# MCU_external_components.net
KiCad netlist of a schematic drawn in Altium Designer
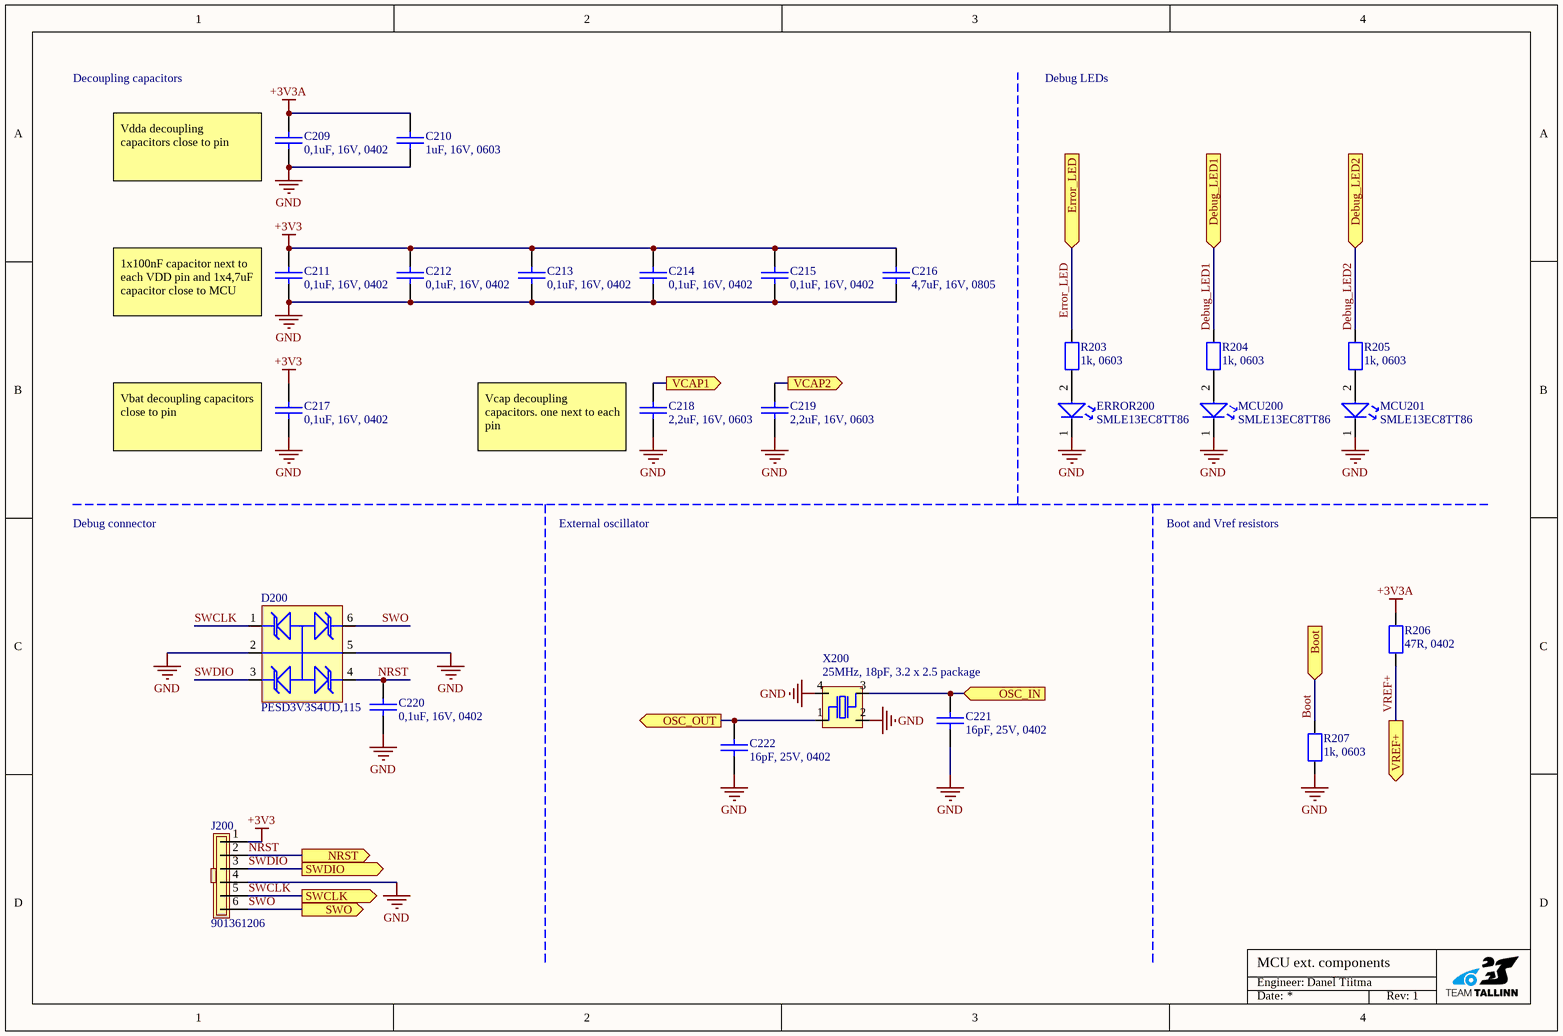
[diagram p0: MCU_external_components.SchDoc]

(export (version "E")
  (design (tool "Eeschema 10.0.6"))
  (components
    (comp (ref "C209")
      (value "0,1uF, 16V, 0402")
      (footprint "CAP [0402] 1005")
      (description "Default capacitor part")
      (libsource (lib "Formula Student Team Tallinn (Estonia)") (part "Capacitor"))
    )
    (comp (ref "C210")
      (value "1uF, 16V, 0603")
      (footprint "CAP [0603] 1608")
      (description "Default capacitor part")
      (libsource (lib "Formula Student Team Tallinn (Estonia)") (part "Capacitor"))
    )
    (comp (ref "C211")
      (value "0,1uF, 16V, 0402")
      (footprint "CAP [0402] 1005")
      (description "Default capacitor part")
      (libsource (lib "Formula Student Team Tallinn (Estonia)") (part "Capacitor"))
    )
    (comp (ref "C212")
      (value "0,1uF, 16V, 0402")
      (footprint "CAP [0402] 1005")
      (description "Default capacitor part")
      (libsource (lib "Formula Student Team Tallinn (Estonia)") (part "Capacitor"))
    )
    (comp (ref "C213")
      (value "0,1uF, 16V, 0402")
      (footprint "CAP [0402] 1005")
      (description "Default capacitor part")
      (libsource (lib "Formula Student Team Tallinn (Estonia)") (part "Capacitor"))
    )
    (comp (ref "C214")
      (value "0,1uF, 16V, 0402")
      (footprint "CAP [0402] 1005")
      (description "Default capacitor part")
      (libsource (lib "Formula Student Team Tallinn (Estonia)") (part "Capacitor"))
    )
    (comp (ref "C215")
      (value "0,1uF, 16V, 0402")
      (footprint "CAP [0402] 1005")
      (description "Default capacitor part")
      (libsource (lib "Formula Student Team Tallinn (Estonia)") (part "Capacitor"))
    )
    (comp (ref "C216")
      (value "4,7uF, 16V, 0805")
      (footprint "CAP [0805] 2012")
      (description "Default capacitor part")
      (libsource (lib "Formula Student Team Tallinn (Estonia)") (part "Capacitor"))
    )
    (comp (ref "C217")
      (value "0,1uF, 16V, 0402")
      (footprint "CAP [0402] 1005")
      (description "Default capacitor part")
      (libsource (lib "Formula Student Team Tallinn (Estonia)") (part "Capacitor"))
    )
    (comp (ref "C218")
      (value "2,2uF, 16V, 0603")
      (footprint "CAP [0603] 1608")
      (fields
        (field (name "MANUFACTURER") "TDK")
        (field (name "MANUFACTURER PART NUMBER") "CGA3E1X5R1C225M080AC")
      )
      (libsource (lib "Formula Student Team Tallinn (Estonia)") (part "Capacitor"))
    )
    (comp (ref "C219")
      (value "2,2uF, 16V, 0603")
      (footprint "CAP [0603] 1608")
      (fields
        (field (name "MANUFACTURER") "TDK")
        (field (name "MANUFACTURER PART NUMBER") "CGA3E1X5R1C225M080AC")
      )
      (libsource (lib "Formula Student Team Tallinn (Estonia)") (part "Capacitor"))
    )
    (comp (ref "C220")
      (value "0,1uF, 16V, 0402")
      (footprint "CAP [0402] 1005")
      (description "Default capacitor part")
      (libsource (lib "Formula Student Team Tallinn (Estonia)") (part "Capacitor"))
    )
    (comp (ref "C221")
      (value "16pF, 25V, 0402")
      (footprint "CAP [0402] 1005")
      (fields
        (field (name "MANUFACTURER PART NUMBER") "C0402C160K3HACAUTO")
        (field (name "MANUFACTURER") "KEMET")
      )
      (libsource (lib "Formula Student Team Tallinn (Estonia)") (part "Capacitor"))
    )
    (comp (ref "C222")
      (value "16pF, 25V, 0402")
      (footprint "CAP [0402] 1005")
      (fields
        (field (name "MANUFACTURER PART NUMBER") "C0402C160K3HACAUTO")
        (field (name "MANUFACTURER") "KEMET")
      )
      (libsource (lib "Formula Student Team Tallinn (Estonia)") (part "Capacitor"))
    )
    (comp (ref "D200")
      (value "PESD3V3S4UD,115")
      (footprint "SOT23-6")
      (description "Trans Voltage Suppressor Diode, 200W, 3.3V V(RWM), Unidirectional, 4 Element, Silicon")
      (fields (field (name "MANUFACTURER") "Nexperia"))
      (libsource (lib "Formula Student Team Tallinn (Estonia)") (part "TVS diode array"))
    )
    (comp (ref "ERROR200")
      (value "SMLE13EC8TT86")
      (footprint "LED [0603] 1608")
      (description "Single Color LED, Green, Colorless Transparent, 1.2mm")
      (libsource (lib "Formula Student Team Tallinn (Estonia)") (part "Diode LED"))
    )
    (comp (ref "J200")
      (value "901361206")
      (footprint "901361206")
      (fields (field (name "MANUFACTURER PART NUMBER") "90136-1206") (field (name "MANUFACTURER") "Molex"))
      (libsource (lib "Formula Student Team Tallinn (Estonia)") (part "Connector C-Grid III 1x6"))
    )
    (comp (ref "MCU200")
      (value "SMLE13EC8TT86")
      (footprint "LED [0603] 1608")
      (description "Single Color LED, Green, Colorless Transparent, 1.2mm")
      (libsource (lib "Formula Student Team Tallinn (Estonia)") (part "Diode LED"))
    )
    (comp (ref "MCU201")
      (value "SMLE13EC8TT86")
      (footprint "LED [0603] 1608")
      (description "Single Color LED, Green, Colorless Transparent, 1.2mm")
      (libsource (lib "Formula Student Team Tallinn (Estonia)") (part "Diode LED"))
    )
    (comp (ref "R203")
      (value "1k, 0603")
      (footprint "RES [0603] 1608")
      (description "Standard resistor part")
      (libsource (lib "Formula Student Team Tallinn (Estonia)") (part "Resistor"))
    )
    (comp (ref "R204")
      (value "1k, 0603")
      (footprint "RES [0603] 1608")
      (description "Standard resistor part")
      (libsource (lib "Formula Student Team Tallinn (Estonia)") (part "Resistor"))
    )
    (comp (ref "R205")
      (value "1k, 0603")
      (footprint "RES [0603] 1608")
      (description "Standard resistor part")
      (libsource (lib "Formula Student Team Tallinn (Estonia)") (part "Resistor"))
    )
    (comp (ref "R206")
      (value "47R, 0402")
      (footprint "RES [0402] 1005")
      (description "Standard resistor part")
      (libsource (lib "Formula Student Team Tallinn (Estonia)") (part "Resistor"))
    )
    (comp (ref "R207")
      (value "1k, 0603")
      (footprint "RES [0603] 1608")
      (description "Standard resistor part")
      (libsource (lib "Formula Student Team Tallinn (Estonia)") (part "Resistor"))
    )
    (comp (ref "X200")
      (value "25MHz, 18pF, 3.2 x 2.5 package")
      (footprint "Crystal 3.2x2.5mm")
      (description "Crystal 25MHz ±20ppm (Tol) ±30ppm (Stability) 18pF FUND 60Ohm 4-Pin Ultra Mini-CSMD T/R")
      (fields
        (field (name "MANUFACTURER PART NUMBER") "ABM8G-25.000MHZ-18-D2Y-T")
        (field (name "MANUFACTURER") "ABRACON")
      )
      (libsource (lib "Formula Student Team Tallinn (Estonia)") (part "Crystal 4-pin"))
    )
  )
  (nets
    (net (code "1") (name "+3V3") (class "Default")
      (node (ref "C211") (pin "2") (pinfunction "2_2") (pintype "passive"))
      (node (ref "C212") (pin "2") (pinfunction "2_2") (pintype "passive"))
      (node (ref "C213") (pin "2") (pinfunction "2_2") (pintype "passive"))
      (node (ref "C214") (pin "2") (pinfunction "2_2") (pintype "passive"))
      (node (ref "C215") (pin "2") (pinfunction "2_2") (pintype "passive"))
      (node (ref "C216") (pin "2") (pinfunction "2_2") (pintype "passive"))
      (node (ref "C217") (pin "2") (pinfunction "2_2") (pintype "passive"))
      (node (ref "J200") (pin "1") (pinfunction "1_1") (pintype "passive"))
    )
    (net (code "2") (name "+3V3A") (class "Default")
      (node (ref "C209") (pin "2") (pinfunction "2_2") (pintype "passive"))
      (node (ref "C210") (pin "2") (pinfunction "2_2") (pintype "passive"))
      (node (ref "R206") (pin "2") (pinfunction "2_2") (pintype "passive"))
    )
    (net (code "3") (name "/Boot") (class "Default")
      (node (ref "R207") (pin "2") (pinfunction "2_2") (pintype "passive"))
    )
    (net (code "4") (name "/Debug_LED1") (class "Default")
      (node (ref "R204") (pin "2") (pinfunction "2_2") (pintype "passive"))
    )
    (net (code "5") (name "/Debug_LED2") (class "Default")
      (node (ref "R205") (pin "2") (pinfunction "2_2") (pintype "passive"))
    )
    (net (code "6") (name "/Error_LED") (class "Default")
      (node (ref "R203") (pin "2") (pinfunction "2_2") (pintype "passive"))
    )
    (net (code "7") (name "/NRST") (class "Default")
      (node (ref "C220") (pin "1") (pinfunction "1_1") (pintype "passive"))
      (node (ref "D200") (pin "4") (pinfunction "K3_4") (pintype "passive"))
      (node (ref "J200") (pin "2") (pinfunction "2_2") (pintype "passive"))
    )
    (net (code "8") (name "/OSC_IN") (class "Default")
      (node (ref "C221") (pin "1") (pinfunction "1_1") (pintype "passive"))
      (node (ref "X200") (pin "3") (pinfunction "3_3") (pintype "passive"))
    )
    (net (code "9") (name "/OSC_OUT") (class "Default")
      (node (ref "C222") (pin "1") (pinfunction "1_1") (pintype "passive"))
      (node (ref "X200") (pin "1") (pinfunction "1_1") (pintype "passive"))
    )
    (net (code "10") (name "/SWCLK") (class "Default")
      (node (ref "D200") (pin "1") (pinfunction "K1_1") (pintype "passive"))
      (node (ref "J200") (pin "5") (pinfunction "5_5") (pintype "passive"))
    )
    (net (code "11") (name "/SWDIO") (class "Default")
      (node (ref "D200") (pin "3") (pinfunction "K2_3") (pintype "passive"))
      (node (ref "J200") (pin "3") (pinfunction "3_3") (pintype "passive"))
    )
    (net (code "12") (name "/SWO") (class "Default")
      (node (ref "D200") (pin "6") (pinfunction "K4_6") (pintype "passive"))
      (node (ref "J200") (pin "6") (pinfunction "6_6") (pintype "passive"))
    )
    (net (code "13") (name "/VCAP1") (class "Default")
      (node (ref "C218") (pin "1") (pinfunction "1_1") (pintype "passive"))
    )
    (net (code "14") (name "/VCAP2") (class "Default")
      (node (ref "C219") (pin "1") (pinfunction "1_1") (pintype "passive"))
    )
    (net (code "15") (name "/VREF+") (class "Default")
      (node (ref "R206") (pin "1") (pinfunction "1_1") (pintype "passive"))
    )
    (net (code "16") (name "GND") (class "Default")
      (node (ref "C209") (pin "1") (pinfunction "1_1") (pintype "passive"))
      (node (ref "C210") (pin "1") (pinfunction "1_1") (pintype "passive"))
      (node (ref "C211") (pin "1") (pinfunction "1_1") (pintype "passive"))
      (node (ref "C212") (pin "1") (pinfunction "1_1") (pintype "passive"))
      (node (ref "C213") (pin "1") (pinfunction "1_1") (pintype "passive"))
      (node (ref "C214") (pin "1") (pinfunction "1_1") (pintype "passive"))
      (node (ref "C215") (pin "1") (pinfunction "1_1") (pintype "passive"))
      (node (ref "C216") (pin "1") (pinfunction "1_1") (pintype "passive"))
      (node (ref "C217") (pin "1") (pinfunction "1_1") (pintype "passive"))
      (node (ref "C218") (pin "2") (pinfunction "2_2") (pintype "passive"))
      (node (ref "C219") (pin "2") (pinfunction "2_2") (pintype "passive"))
      (node (ref "C220") (pin "2") (pinfunction "2_2") (pintype "passive"))
      (node (ref "C221") (pin "2") (pinfunction "2_2") (pintype "passive"))
      (node (ref "C222") (pin "2") (pinfunction "2_2") (pintype "passive"))
      (node (ref "D200") (pin "2") (pinfunction "GND_2") (pintype "passive"))
      (node (ref "D200") (pin "5") (pinfunction "GND_5") (pintype "passive"))
      (node (ref "ERROR200") (pin "1") (pinfunction "1_1") (pintype "passive"))
      (node (ref "J200") (pin "4") (pinfunction "4_4") (pintype "passive"))
      (node (ref "MCU200") (pin "1") (pinfunction "1_1") (pintype "passive"))
      (node (ref "MCU201") (pin "1") (pinfunction "1_1") (pintype "passive"))
      (node (ref "R207") (pin "1") (pinfunction "1_1") (pintype "passive"))
      (node (ref "X200") (pin "2") (pinfunction "2_2") (pintype "passive"))
      (node (ref "X200") (pin "4") (pinfunction "4_4") (pintype "passive"))
    )
    (net (code "17") (name "Net-(ERROR200-Pad2)") (class "Default")
      (node (ref "ERROR200") (pin "2") (pinfunction "2_2") (pintype "passive"))
      (node (ref "R203") (pin "1") (pinfunction "1_1") (pintype "passive"))
    )
    (net (code "18") (name "Net-(MCU200-Pad2)") (class "Default")
      (node (ref "MCU200") (pin "2") (pinfunction "2_2") (pintype "passive"))
      (node (ref "R204") (pin "1") (pinfunction "1_1") (pintype "passive"))
    )
    (net (code "19") (name "Net-(MCU201-Pad2)") (class "Default")
      (node (ref "MCU201") (pin "2") (pinfunction "2_2") (pintype "passive"))
      (node (ref "R205") (pin "1") (pinfunction "1_1") (pintype "passive"))
    )
  )
)
